# Sheet2.net
KiCad netlist of a schematic drawn in Altium Designer
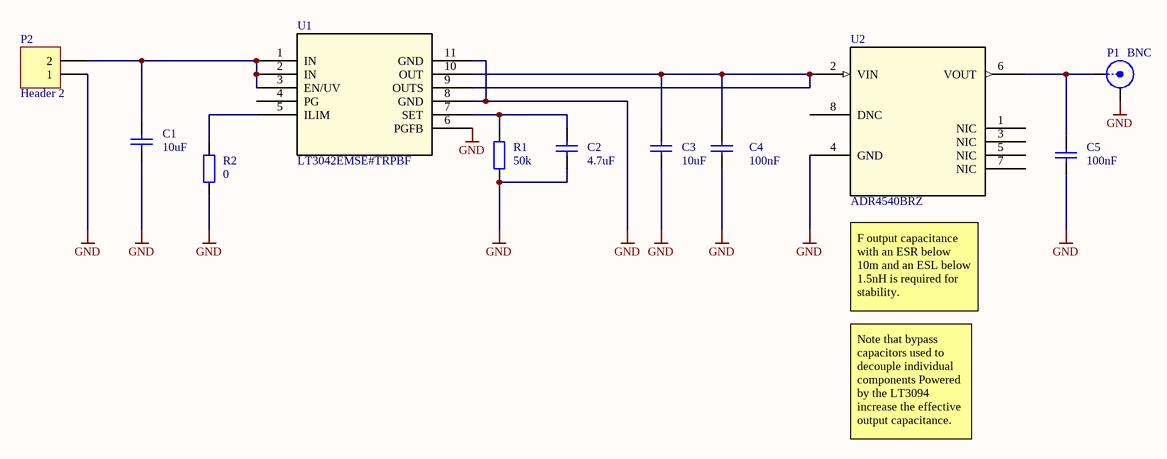
[diagram p0: Sheet2.SchDoc]

(export (version "E")
  (design (tool "Eeschema 10.0.6"))
  (components
    (comp (ref "C1")
      (value "10uF")
      (footprint "C1206-KUE")
      (description "Capacitor")
      (fields (field (name "MANUFACTURER") "Kemet") (field (name "PUBLISHER") "Altium Limited"))
      (libsource (lib "ExtrapartsKUE_V01") (part "Capacitor"))
    )
    (comp (ref "C2")
      (value "4.7uF")
      (footprint "C1206-KUE")
      (description "Capacitor X7R")
      (fields (field (name "MANUFACTURER") "Kemet") (field (name "PUBLISHER") "Altium Limited"))
      (libsource (lib "ExtrapartsKUE_V01") (part "Capacitor"))
    )
    (comp (ref "C3")
      (value "10uF")
      (footprint "C1206-KUE")
      (description "Capacitor X7R")
      (fields (field (name "MANUFACTURER") "Kemet") (field (name "PUBLISHER") "Altium Limited"))
      (libsource (lib "ExtrapartsKUE_V01") (part "Capacitor"))
    )
    (comp (ref "C4")
      (value "100nF")
      (footprint "C1206-KUE")
      (description "Capacitor X7R")
      (fields (field (name "MANUFACTURER") "Kemet") (field (name "PUBLISHER") "Altium Limited"))
      (libsource (lib "ExtrapartsKUE_V01") (part "Capacitor"))
    )
    (comp (ref "C5")
      (value "100nF")
      (footprint "C1206-KUE")
      (description "Capacitor X7r")
      (fields (field (name "MANUFACTURER") "Kemet") (field (name "PUBLISHER") "Altium Limited"))
      (libsource (lib "ExtrapartsKUE_V01") (part "Capacitor"))
    )
    (comp (ref "P1")
      (value "BNC")
      (footprint "BNC_RA CON")
      (description "BNC Elbow Connector")
      (fields (field (name "PUBLISHER") "Altium Limited"))
      (libsource (lib "Miscellaneous Connectors") (part "BNC"))
    )
    (comp (ref "P2")
      (value "Header 2")
      (footprint "HDR1X2")
      (description "Header, 2-Pin")
      (fields (field (name "PUBLISHER") "Altium Limited"))
      (libsource (lib "Miscellaneous Connectors") (part "Header 2"))
    )
    (comp (ref "R1")
      (value "50k")
      (footprint "C1206-KUE")
      (description "Resistor SMD 1%")
      (fields (field (name "MANUFACTURER") "AVX") (field (name "PUBLISHER") "Altium Limited"))
      (libsource (lib "ExtrapartsKUE_V01") (part "ResistorSMD"))
    )
    (comp (ref "R2")
      (value "0")
      (footprint "C1206-KUE")
      (description "Resistor SMD")
      (fields (field (name "MANUFACTURER") "AVX") (field (name "PUBLISHER") "Altium Limited"))
      (libsource (lib "ExtrapartsKUE_V01") (part "ResistorSMD"))
    )
    (comp (ref "U1")
      (value "LT3042EMSE#TRPBF")
      (footprint "05-08-1664_ADI")
      (description "20V, 200mA, Ultralow Noise, Ultrahigh PSRR RF Linear Regulator")
      (fields (field (name "COPYRIGHT") "Copyright (C) 2025 Ultra Librarian. All rights reserved."))
      (libsource (lib "MyOwnParts") (part "LT3042EMSETRPBF"))
    )
    (comp (ref "U2")
      (value "ADR4540BRZ")
      (footprint "R-8_ADI")
      (description "Ultra-Low-Noise, High-Accuracy 4.096V Voltage Reference")
      (fields (field (name "COPYRIGHT") "Copyright (C) 2025 Ultra Librarian. All rights reserved."))
      (libsource (lib "ADR4540BRZ") (part "ADR4540BRZ"))
    )
  )
  (nets
    (net (code "1") (name "GND") (class "Default")
      (node (ref "C1") (pin "1") (pinfunction "1_1") (pintype "passive"))
      (node (ref "C2") (pin "1") (pinfunction "1_1") (pintype "passive"))
      (node (ref "C3") (pin "1") (pinfunction "1_1") (pintype "passive"))
      (node (ref "C4") (pin "1") (pinfunction "1_1") (pintype "passive"))
      (node (ref "C5") (pin "1") (pinfunction "1_1") (pintype "passive"))
      (node (ref "P1") (pin "2") (pinfunction "Y_2") (pintype "passive"))
      (node (ref "P2") (pin "1") (pinfunction "1_1") (pintype "passive"))
      (node (ref "R1") (pin "2") (pinfunction "2_2") (pintype "passive"))
      (node (ref "R2") (pin "2") (pinfunction "2_2") (pintype "passive"))
      (node (ref "U1") (pin "11") (pinfunction "GND_11") (pintype "power_in"))
      (node (ref "U1") (pin "6") (pinfunction "PGFB_6") (pintype "passive"))
      (node (ref "U1") (pin "8") (pinfunction "GND_8") (pintype "power_in"))
      (node (ref "U2") (pin "4") (pinfunction "GND_4") (pintype "power_in"))
    )
    (net (code "2") (name "Net-(P1-X)") (class "Default")
      (node (ref "C5") (pin "2") (pinfunction "2_2") (pintype "passive"))
      (node (ref "P1") (pin "1") (pinfunction "X_1") (pintype "passive"))
      (node (ref "U2") (pin "6") (pinfunction "VOUT_6") (pintype "output"))
    )
    (net (code "3") (name "Net-(U1-EN{slash}UV)") (class "Default")
      (node (ref "C1") (pin "2") (pinfunction "2_2") (pintype "passive"))
      (node (ref "P2") (pin "2") (pinfunction "2_2") (pintype "passive"))
      (node (ref "U1") (pin "1") (pinfunction "IN_1") (pintype "power_in"))
      (node (ref "U1") (pin "2") (pinfunction "IN_2") (pintype "power_in"))
      (node (ref "U1") (pin "3") (pinfunction "EN/UV_3") (pintype "passive"))
    )
    (net (code "4") (name "Net-(U1-ILIM)") (class "Default")
      (node (ref "R2") (pin "1") (pinfunction "1_1") (pintype "passive"))
      (node (ref "U1") (pin "5") (pinfunction "ILIM_5") (pintype "passive"))
    )
    (net (code "5") (name "Net-(U1-OUT)") (class "Default")
      (node (ref "C3") (pin "2") (pinfunction "2_2") (pintype "passive"))
      (node (ref "C4") (pin "2") (pinfunction "2_2") (pintype "passive"))
      (node (ref "U1") (pin "10") (pinfunction "OUT_10") (pintype "passive"))
      (node (ref "U1") (pin "9") (pinfunction "OUTS_9") (pintype "passive"))
      (node (ref "U2") (pin "2") (pinfunction "VIN_2") (pintype "input"))
    )
    (net (code "6") (name "Net-(U1-SET)") (class "Default")
      (node (ref "C2") (pin "2") (pinfunction "2_2") (pintype "passive"))
      (node (ref "R1") (pin "1") (pinfunction "1_1") (pintype "passive"))
      (node (ref "U1") (pin "7") (pinfunction "SET_7") (pintype "passive"))
    )
    (net (code "7") (name "unconnected-(U1-PG-Pad4)") (class "Default")
      (node (ref "U1") (pin "4") (pinfunction "PG_4") (pintype "passive"))
    )
    (net (code "8") (name "unconnected-(U2-DNC-Pad8)") (class "Default")
      (node (ref "U2") (pin "8") (pinfunction "DNC_8") (pintype "passive"))
    )
    (net (code "9") (name "unconnected-(U2-NIC-Pad1)") (class "Default")
      (node (ref "U2") (pin "1") (pinfunction "NIC_1") (pintype "passive"))
    )
    (net (code "10") (name "unconnected-(U2-NIC-Pad3)") (class "Default")
      (node (ref "U2") (pin "3") (pinfunction "NIC_3") (pintype "passive"))
    )
    (net (code "11") (name "unconnected-(U2-NIC-Pad5)") (class "Default")
      (node (ref "U2") (pin "5") (pinfunction "NIC_5") (pintype "passive"))
    )
    (net (code "12") (name "unconnected-(U2-NIC-Pad7)") (class "Default")
      (node (ref "U2") (pin "7") (pinfunction "NIC_7") (pintype "passive"))
    )
  )
)
